# analog_part.net
KiCad netlist of a schematic drawn in Altium Designer
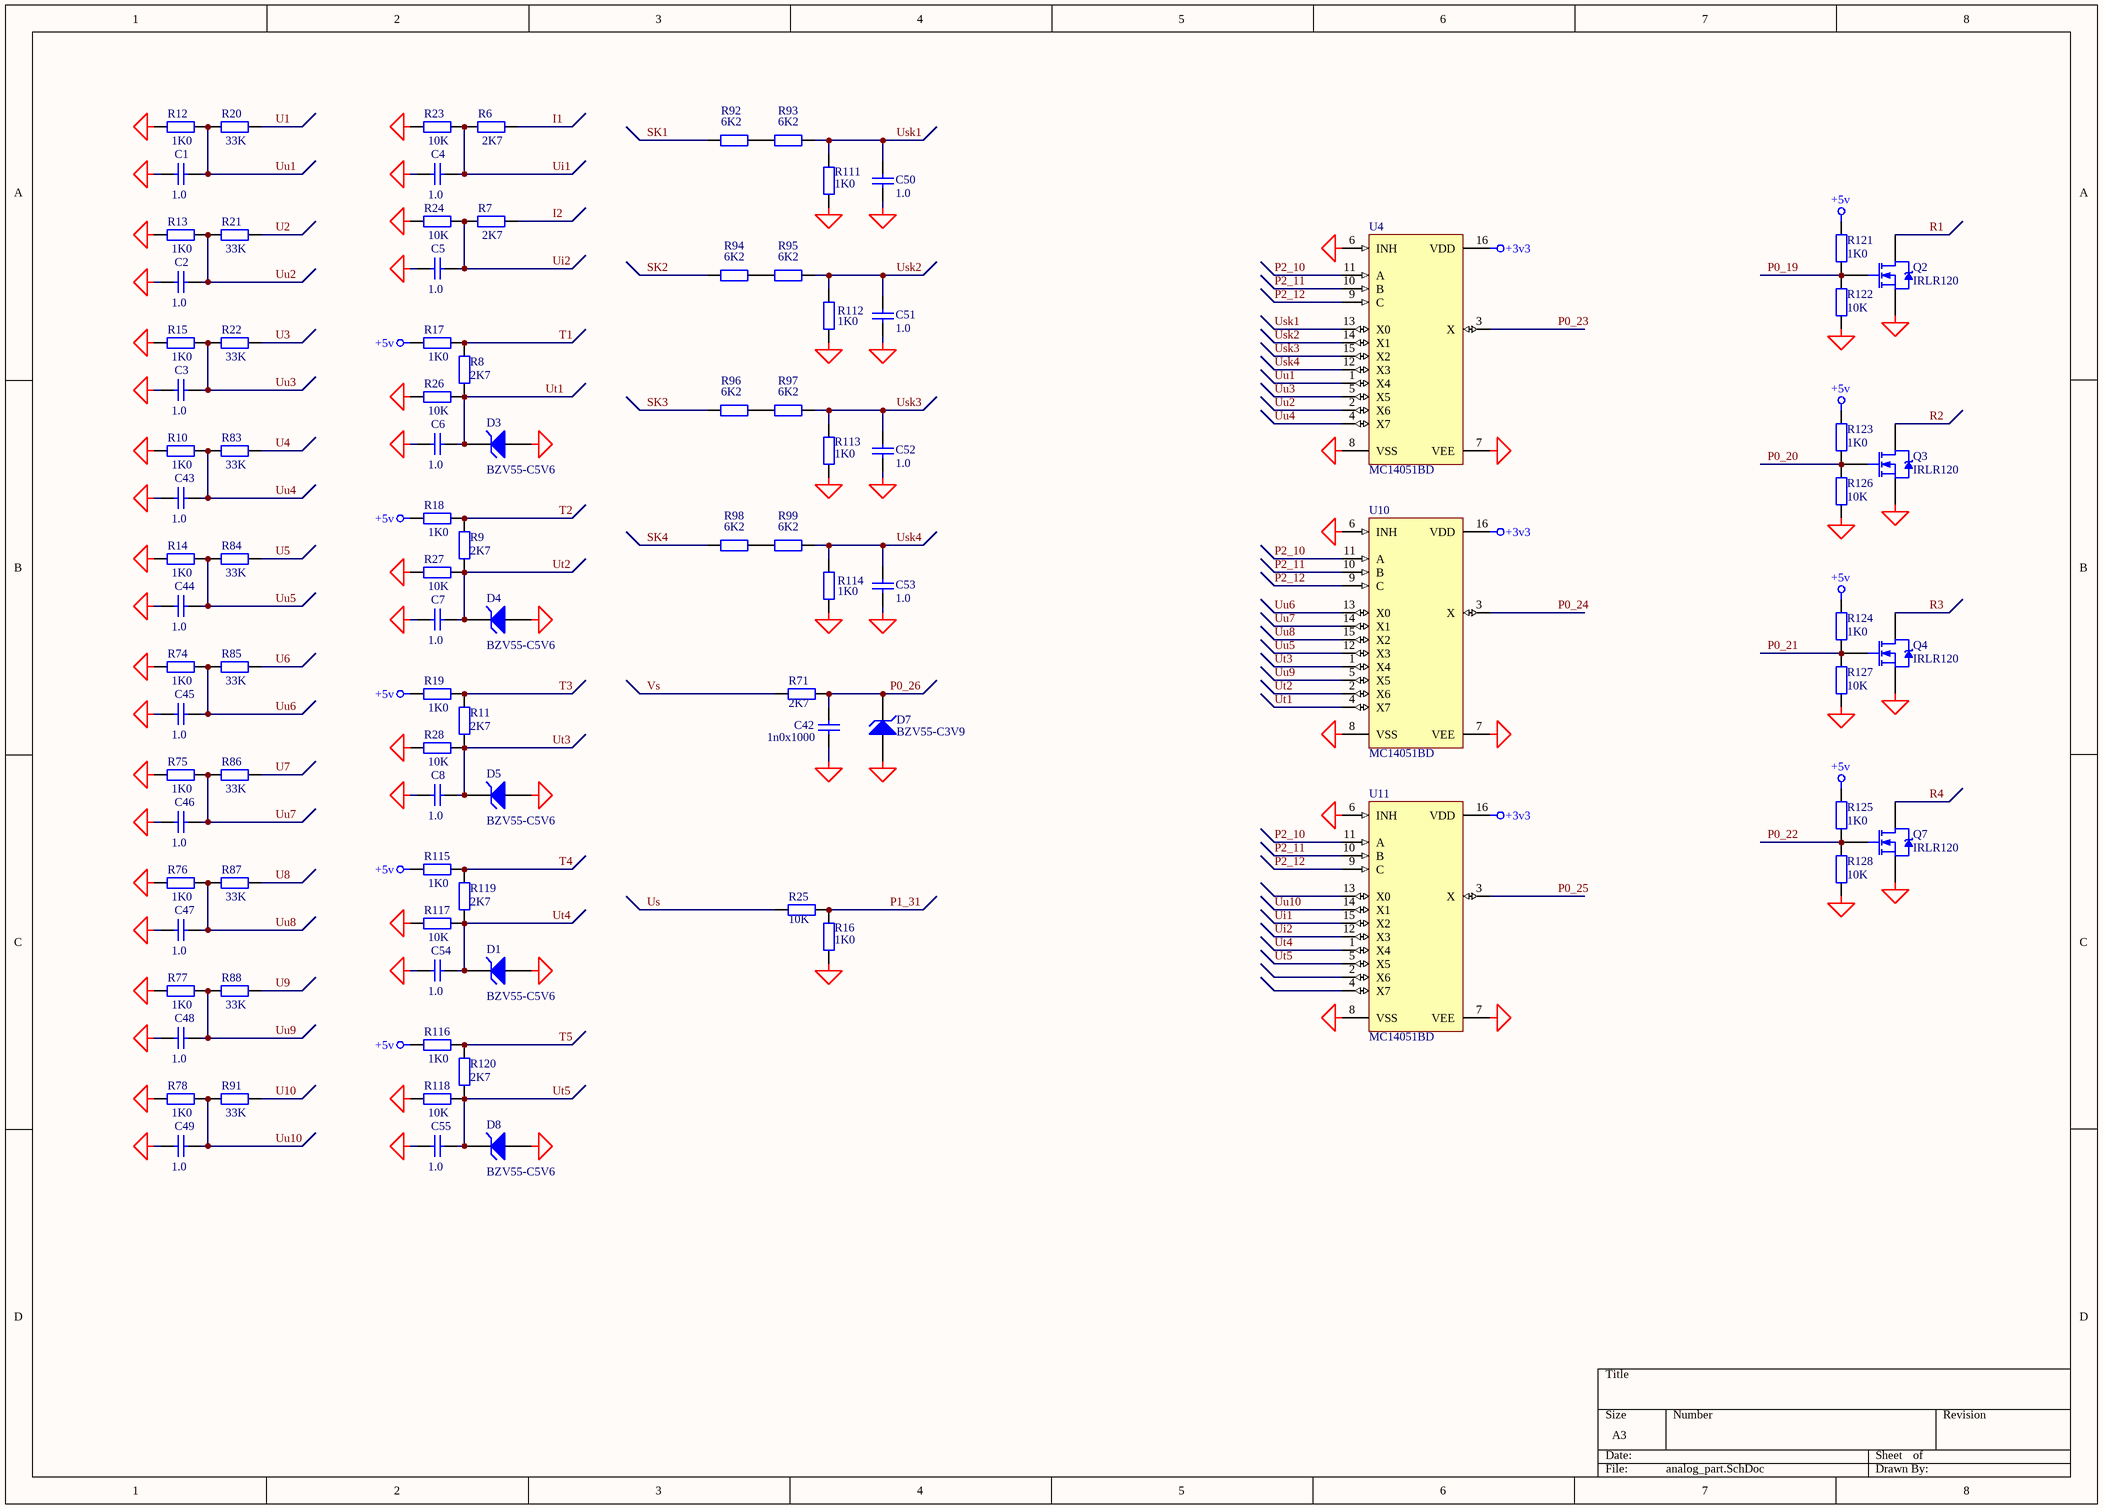
[diagram p0: analog_part.SchDoc]

(export (version "E")
  (design (tool "Eeschema 10.0.6"))
  (components
    (comp (ref "C1")
      (value "1.0")
      (footprint "_1206")
      (description "Capacitor (Semiconductor SIM Model)")
      (fields (field (name "MANUFACTURER") "Generic Components") (field (name "PUBLISHER") "Altium Limited"))
      (libsource (lib "Miscellaneous Devices") (part "Cap Semi"))
    )
    (comp (ref "C2")
      (value "1.0")
      (footprint "_1206")
      (description "Capacitor (Semiconductor SIM Model)")
      (fields (field (name "MANUFACTURER") "Generic Components") (field (name "PUBLISHER") "Altium Limited"))
      (libsource (lib "Miscellaneous Devices") (part "Cap Semi"))
    )
    (comp (ref "C3")
      (value "1.0")
      (footprint "_1206")
      (description "Capacitor (Semiconductor SIM Model)")
      (fields (field (name "MANUFACTURER") "Generic Components") (field (name "PUBLISHER") "Altium Limited"))
      (libsource (lib "Miscellaneous Devices") (part "Cap Semi"))
    )
    (comp (ref "C4")
      (value "1.0")
      (footprint "_1206")
      (description "Capacitor (Semiconductor SIM Model)")
      (fields (field (name "MANUFACTURER") "Generic Components") (field (name "PUBLISHER") "Altium Limited"))
      (libsource (lib "Miscellaneous Devices") (part "Cap Semi"))
    )
    (comp (ref "C5")
      (value "1.0")
      (footprint "_1206")
      (description "Capacitor (Semiconductor SIM Model)")
      (fields (field (name "MANUFACTURER") "Generic Components") (field (name "PUBLISHER") "Altium Limited"))
      (libsource (lib "Miscellaneous Devices") (part "Cap Semi"))
    )
    (comp (ref "C6")
      (value "1.0")
      (footprint "_1206")
      (description "Capacitor (Semiconductor SIM Model)")
      (fields (field (name "MANUFACTURER") "Generic Components") (field (name "PUBLISHER") "Altium Limited"))
      (libsource (lib "Miscellaneous Devices") (part "Cap Semi"))
    )
    (comp (ref "C7")
      (value "1.0")
      (footprint "_1206")
      (description "Capacitor (Semiconductor SIM Model)")
      (fields (field (name "MANUFACTURER") "Generic Components") (field (name "PUBLISHER") "Altium Limited"))
      (libsource (lib "Miscellaneous Devices") (part "Cap Semi"))
    )
    (comp (ref "C8")
      (value "1.0")
      (footprint "_1206")
      (description "Capacitor (Semiconductor SIM Model)")
      (fields (field (name "MANUFACTURER") "Generic Components") (field (name "PUBLISHER") "Altium Limited"))
      (libsource (lib "Miscellaneous Devices") (part "Cap Semi"))
    )
    (comp (ref "C42")
      (value "1n0x1000")
      (footprint "_1206")
      (description "Capacitor (Semiconductor SIM Model)")
      (fields (field (name "MANUFACTURER") "Generic Components") (field (name "PUBLISHER") "Altium Limited"))
      (libsource (lib "") (part "Cap Semi_1"))
    )
    (comp (ref "C43")
      (value "1.0")
      (footprint "_1206")
      (description "Capacitor (Semiconductor SIM Model)")
      (fields (field (name "MANUFACTURER") "Generic Components") (field (name "PUBLISHER") "Altium Limited"))
      (libsource (lib "Miscellaneous Devices") (part "Cap Semi"))
    )
    (comp (ref "C44")
      (value "1.0")
      (footprint "_1206")
      (description "Capacitor (Semiconductor SIM Model)")
      (fields (field (name "MANUFACTURER") "Generic Components") (field (name "PUBLISHER") "Altium Limited"))
      (libsource (lib "Miscellaneous Devices") (part "Cap Semi"))
    )
    (comp (ref "C45")
      (value "1.0")
      (footprint "_1206")
      (description "Capacitor (Semiconductor SIM Model)")
      (fields (field (name "MANUFACTURER") "Generic Components") (field (name "PUBLISHER") "Altium Limited"))
      (libsource (lib "Miscellaneous Devices") (part "Cap Semi"))
    )
    (comp (ref "C46")
      (value "1.0")
      (footprint "_1206")
      (description "Capacitor (Semiconductor SIM Model)")
      (fields (field (name "MANUFACTURER") "Generic Components") (field (name "PUBLISHER") "Altium Limited"))
      (libsource (lib "Miscellaneous Devices") (part "Cap Semi"))
    )
    (comp (ref "C47")
      (value "1.0")
      (footprint "_1206")
      (description "Capacitor (Semiconductor SIM Model)")
      (fields (field (name "MANUFACTURER") "Generic Components") (field (name "PUBLISHER") "Altium Limited"))
      (libsource (lib "Miscellaneous Devices") (part "Cap Semi"))
    )
    (comp (ref "C48")
      (value "1.0")
      (footprint "_1206")
      (description "Capacitor (Semiconductor SIM Model)")
      (fields (field (name "MANUFACTURER") "Generic Components") (field (name "PUBLISHER") "Altium Limited"))
      (libsource (lib "Miscellaneous Devices") (part "Cap Semi"))
    )
    (comp (ref "C49")
      (value "1.0")
      (footprint "_1206")
      (description "Capacitor (Semiconductor SIM Model)")
      (fields (field (name "MANUFACTURER") "Generic Components") (field (name "PUBLISHER") "Altium Limited"))
      (libsource (lib "Miscellaneous Devices") (part "Cap Semi"))
    )
    (comp (ref "C50")
      (value "1.0")
      (footprint "_1206")
      (description "Capacitor (Semiconductor SIM Model)")
      (fields (field (name "MANUFACTURER") "Generic Components") (field (name "PUBLISHER") "Altium Limited"))
      (libsource (lib "Miscellaneous Devices") (part "Cap Semi"))
    )
    (comp (ref "C51")
      (value "1.0")
      (footprint "_1206")
      (description "Capacitor (Semiconductor SIM Model)")
      (fields (field (name "MANUFACTURER") "Generic Components") (field (name "PUBLISHER") "Altium Limited"))
      (libsource (lib "Miscellaneous Devices") (part "Cap Semi"))
    )
    (comp (ref "C52")
      (value "1.0")
      (footprint "_1206")
      (description "Capacitor (Semiconductor SIM Model)")
      (fields (field (name "MANUFACTURER") "Generic Components") (field (name "PUBLISHER") "Altium Limited"))
      (libsource (lib "Miscellaneous Devices") (part "Cap Semi"))
    )
    (comp (ref "C53")
      (value "1.0")
      (footprint "_1206")
      (description "Capacitor (Semiconductor SIM Model)")
      (fields (field (name "MANUFACTURER") "Generic Components") (field (name "PUBLISHER") "Altium Limited"))
      (libsource (lib "Miscellaneous Devices") (part "Cap Semi"))
    )
    (comp (ref "C54")
      (value "1.0")
      (footprint "_1206")
      (description "Capacitor (Semiconductor SIM Model)")
      (fields (field (name "MANUFACTURER") "Generic Components") (field (name "PUBLISHER") "Altium Limited"))
      (libsource (lib "Miscellaneous Devices") (part "Cap Semi"))
    )
    (comp (ref "C55")
      (value "1.0")
      (footprint "_1206")
      (description "Capacitor (Semiconductor SIM Model)")
      (fields (field (name "MANUFACTURER") "Generic Components") (field (name "PUBLISHER") "Altium Limited"))
      (libsource (lib "Miscellaneous Devices") (part "Cap Semi"))
    )
    (comp (ref "D1")
      (value "BZV55-C5V6")
      (footprint "_1206d")
      (description "Zener Diode")
      (fields (field (name "MANUFACTURER") "Generic Components") (field (name "PUBLISHER") "Altium Limited"))
      (libsource (lib "Miscellaneous Devices") (part "D Zener"))
    )
    (comp (ref "D3")
      (value "BZV55-C5V6")
      (footprint "_1206d")
      (description "Zener Diode")
      (fields (field (name "MANUFACTURER") "Generic Components") (field (name "PUBLISHER") "Altium Limited"))
      (libsource (lib "Miscellaneous Devices") (part "D Zener"))
    )
    (comp (ref "D4")
      (value "BZV55-C5V6")
      (footprint "_1206d")
      (description "Zener Diode")
      (fields (field (name "MANUFACTURER") "Generic Components") (field (name "PUBLISHER") "Altium Limited"))
      (libsource (lib "Miscellaneous Devices") (part "D Zener"))
    )
    (comp (ref "D5")
      (value "BZV55-C5V6")
      (footprint "_1206d")
      (description "Zener Diode")
      (fields (field (name "MANUFACTURER") "Generic Components") (field (name "PUBLISHER") "Altium Limited"))
      (libsource (lib "Miscellaneous Devices") (part "D Zener"))
    )
    (comp (ref "D7")
      (value "BZV55-C3V9")
      (footprint "_1206d")
      (description "Zener Diode")
      (fields (field (name "MANUFACTURER") "Generic Components") (field (name "PUBLISHER") "Altium Limited"))
      (libsource (lib "") (part "D Zener_1"))
    )
    (comp (ref "D8")
      (value "BZV55-C5V6")
      (footprint "_1206d")
      (description "Zener Diode")
      (fields (field (name "MANUFACTURER") "Generic Components") (field (name "PUBLISHER") "Altium Limited"))
      (libsource (lib "Miscellaneous Devices") (part "D Zener"))
    )
    (comp (ref "Q2")
      (value "IRLR120")
      (footprint "SIP-G3/E8")
      (description "HEXFET N-Channel Power MOSFET")
      (fields
        (field (name "MANUFACTURER") "International Rectifier")
        (field (name "PUBLISHER") "Altium Limited")
      )
      (libsource (lib "IR Discrete MOSFET") (part "IRFR120"))
    )
    (comp (ref "Q3")
      (value "IRLR120")
      (footprint "SIP-G3/E8")
      (description "HEXFET N-Channel Power MOSFET")
      (fields
        (field (name "MANUFACTURER") "International Rectifier")
        (field (name "PUBLISHER") "Altium Limited")
      )
      (libsource (lib "IR Discrete MOSFET") (part "IRFR120"))
    )
    (comp (ref "Q4")
      (value "IRLR120")
      (footprint "SIP-G3/E8")
      (description "HEXFET N-Channel Power MOSFET")
      (fields
        (field (name "MANUFACTURER") "International Rectifier")
        (field (name "PUBLISHER") "Altium Limited")
      )
      (libsource (lib "IR Discrete MOSFET") (part "IRFR120"))
    )
    (comp (ref "Q7")
      (value "IRLR120")
      (footprint "SIP-G3/E8")
      (description "HEXFET N-Channel Power MOSFET")
      (fields
        (field (name "MANUFACTURER") "International Rectifier")
        (field (name "PUBLISHER") "Altium Limited")
      )
      (libsource (lib "IR Discrete MOSFET") (part "IRFR120"))
    )
    (comp (ref "R6")
      (value "2K7")
      (footprint "_1206")
      (description "Resistor")
      (fields (field (name "MANUFACTURER") "Generic Components") (field (name "PUBLISHER") "Altium Limited"))
      (libsource (lib "") (part "Res2_2"))
    )
    (comp (ref "R7")
      (value "2K7")
      (footprint "_1206")
      (description "Resistor")
      (fields (field (name "MANUFACTURER") "Generic Components") (field (name "PUBLISHER") "Altium Limited"))
      (libsource (lib "") (part "Res2_2"))
    )
    (comp (ref "R8")
      (value "2K7")
      (footprint "_1206")
      (description "Resistor")
      (fields (field (name "MANUFACTURER") "Generic Components") (field (name "PUBLISHER") "Altium Limited"))
      (libsource (lib "Miscellaneous Devices") (part "Res2"))
    )
    (comp (ref "R9")
      (value "2K7")
      (footprint "_1206")
      (description "Resistor")
      (fields (field (name "MANUFACTURER") "Generic Components") (field (name "PUBLISHER") "Altium Limited"))
      (libsource (lib "Miscellaneous Devices") (part "Res2"))
    )
    (comp (ref "R10")
      (value "1K0")
      (footprint "_1206")
      (description "Resistor")
      (fields (field (name "MANUFACTURER") "Generic Components") (field (name "PUBLISHER") "Altium Limited"))
      (libsource (lib "") (part "Res2_1"))
    )
    (comp (ref "R11")
      (value "2K7")
      (footprint "_1206")
      (description "Resistor")
      (fields (field (name "MANUFACTURER") "Generic Components") (field (name "PUBLISHER") "Altium Limited"))
      (libsource (lib "Miscellaneous Devices") (part "Res2"))
    )
    (comp (ref "R12")
      (value "1K0")
      (footprint "_1206")
      (description "Resistor")
      (fields (field (name "MANUFACTURER") "Generic Components") (field (name "PUBLISHER") "Altium Limited"))
      (libsource (lib "") (part "Res2_1"))
    )
    (comp (ref "R13")
      (value "1K0")
      (footprint "_1206")
      (description "Resistor")
      (fields (field (name "MANUFACTURER") "Generic Components") (field (name "PUBLISHER") "Altium Limited"))
      (libsource (lib "") (part "Res2_1"))
    )
    (comp (ref "R14")
      (value "1K0")
      (footprint "_1206")
      (description "Resistor")
      (fields (field (name "MANUFACTURER") "Generic Components") (field (name "PUBLISHER") "Altium Limited"))
      (libsource (lib "") (part "Res2_1"))
    )
    (comp (ref "R15")
      (value "1K0")
      (footprint "_1206")
      (description "Resistor")
      (fields (field (name "MANUFACTURER") "Generic Components") (field (name "PUBLISHER") "Altium Limited"))
      (libsource (lib "") (part "Res2_1"))
    )
    (comp (ref "R16")
      (value "1K0")
      (footprint "_1206")
      (description "Resistor")
      (fields (field (name "MANUFACTURER") "Generic Components") (field (name "PUBLISHER") "Altium Limited"))
      (libsource (lib "") (part "Res2_3"))
    )
    (comp (ref "R17")
      (value "1K0")
      (footprint "_1206")
      (description "Resistor")
      (fields (field (name "MANUFACTURER") "Generic Components") (field (name "PUBLISHER") "Altium Limited"))
      (libsource (lib "") (part "Res2_1"))
    )
    (comp (ref "R18")
      (value "1K0")
      (footprint "_1206")
      (description "Resistor")
      (fields (field (name "MANUFACTURER") "Generic Components") (field (name "PUBLISHER") "Altium Limited"))
      (libsource (lib "") (part "Res2_1"))
    )
    (comp (ref "R19")
      (value "1K0")
      (footprint "_1206")
      (description "Resistor")
      (fields (field (name "MANUFACTURER") "Generic Components") (field (name "PUBLISHER") "Altium Limited"))
      (libsource (lib "") (part "Res2_1"))
    )
    (comp (ref "R20")
      (value "33K")
      (footprint "_1206")
      (description "Resistor")
      (fields (field (name "MANUFACTURER") "Generic Components") (field (name "PUBLISHER") "Altium Limited"))
      (libsource (lib "") (part "Res2_2"))
    )
    (comp (ref "R21")
      (value "33K")
      (footprint "_1206")
      (description "Resistor")
      (fields (field (name "MANUFACTURER") "Generic Components") (field (name "PUBLISHER") "Altium Limited"))
      (libsource (lib "") (part "Res2_2"))
    )
    (comp (ref "R22")
      (value "33K")
      (footprint "_1206")
      (description "Resistor")
      (fields (field (name "MANUFACTURER") "Generic Components") (field (name "PUBLISHER") "Altium Limited"))
      (libsource (lib "") (part "Res2_2"))
    )
    (comp (ref "R23")
      (value "10K")
      (footprint "_1206")
      (description "Resistor")
      (fields (field (name "MANUFACTURER") "Generic Components") (field (name "PUBLISHER") "Altium Limited"))
      (libsource (lib "") (part "Res2_2"))
    )
    (comp (ref "R24")
      (value "10K")
      (footprint "_1206")
      (description "Resistor")
      (fields (field (name "MANUFACTURER") "Generic Components") (field (name "PUBLISHER") "Altium Limited"))
      (libsource (lib "") (part "Res2_2"))
    )
    (comp (ref "R25")
      (value "10K")
      (footprint "_1206")
      (description "Resistor")
      (fields (field (name "MANUFACTURER") "Generic Components") (field (name "PUBLISHER") "Altium Limited"))
      (libsource (lib "") (part "Res2_1"))
    )
    (comp (ref "R26")
      (value "10K")
      (footprint "_1206")
      (description "Resistor")
      (fields (field (name "MANUFACTURER") "Generic Components") (field (name "PUBLISHER") "Altium Limited"))
      (libsource (lib "") (part "Res2_2"))
    )
    (comp (ref "R27")
      (value "10K")
      (footprint "_1206")
      (description "Resistor")
      (fields (field (name "MANUFACTURER") "Generic Components") (field (name "PUBLISHER") "Altium Limited"))
      (libsource (lib "") (part "Res2_2"))
    )
    (comp (ref "R28")
      (value "10K")
      (footprint "_1206")
      (description "Resistor")
      (fields (field (name "MANUFACTURER") "Generic Components") (field (name "PUBLISHER") "Altium Limited"))
      (libsource (lib "") (part "Res2_2"))
    )
    (comp (ref "R71")
      (value "2K7")
      (footprint "_1206")
      (description "Resistor")
      (fields (field (name "MANUFACTURER") "Generic Components") (field (name "PUBLISHER") "Altium Limited"))
      (libsource (lib "") (part "Res2_4"))
    )
    (comp (ref "R74")
      (value "1K0")
      (footprint "_1206")
      (description "Resistor")
      (fields (field (name "MANUFACTURER") "Generic Components") (field (name "PUBLISHER") "Altium Limited"))
      (libsource (lib "") (part "Res2_1"))
    )
    (comp (ref "R75")
      (value "1K0")
      (footprint "_1206")
      (description "Resistor")
      (fields (field (name "MANUFACTURER") "Generic Components") (field (name "PUBLISHER") "Altium Limited"))
      (libsource (lib "") (part "Res2_1"))
    )
    (comp (ref "R76")
      (value "1K0")
      (footprint "_1206")
      (description "Resistor")
      (fields (field (name "MANUFACTURER") "Generic Components") (field (name "PUBLISHER") "Altium Limited"))
      (libsource (lib "") (part "Res2_1"))
    )
    (comp (ref "R77")
      (value "1K0")
      (footprint "_1206")
      (description "Resistor")
      (fields (field (name "MANUFACTURER") "Generic Components") (field (name "PUBLISHER") "Altium Limited"))
      (libsource (lib "") (part "Res2_1"))
    )
    (comp (ref "R78")
      (value "1K0")
      (footprint "_1206")
      (description "Resistor")
      (fields (field (name "MANUFACTURER") "Generic Components") (field (name "PUBLISHER") "Altium Limited"))
      (libsource (lib "") (part "Res2_1"))
    )
    (comp (ref "R83")
      (value "33K")
      (footprint "_1206")
      (description "Resistor")
      (fields (field (name "MANUFACTURER") "Generic Components") (field (name "PUBLISHER") "Altium Limited"))
      (libsource (lib "") (part "Res2_2"))
    )
    (comp (ref "R84")
      (value "33K")
      (footprint "_1206")
      (description "Resistor")
      (fields (field (name "MANUFACTURER") "Generic Components") (field (name "PUBLISHER") "Altium Limited"))
      (libsource (lib "") (part "Res2_2"))
    )
    (comp (ref "R85")
      (value "33K")
      (footprint "_1206")
      (description "Resistor")
      (fields (field (name "MANUFACTURER") "Generic Components") (field (name "PUBLISHER") "Altium Limited"))
      (libsource (lib "") (part "Res2_2"))
    )
    (comp (ref "R86")
      (value "33K")
      (footprint "_1206")
      (description "Resistor")
      (fields (field (name "MANUFACTURER") "Generic Components") (field (name "PUBLISHER") "Altium Limited"))
      (libsource (lib "") (part "Res2_2"))
    )
    (comp (ref "R87")
      (value "33K")
      (footprint "_1206")
      (description "Resistor")
      (fields (field (name "MANUFACTURER") "Generic Components") (field (name "PUBLISHER") "Altium Limited"))
      (libsource (lib "") (part "Res2_2"))
    )
    (comp (ref "R88")
      (value "33K")
      (footprint "_1206")
      (description "Resistor")
      (fields (field (name "MANUFACTURER") "Generic Components") (field (name "PUBLISHER") "Altium Limited"))
      (libsource (lib "") (part "Res2_2"))
    )
    (comp (ref "R91")
      (value "33K")
      (footprint "_1206")
      (description "Resistor")
      (fields (field (name "MANUFACTURER") "Generic Components") (field (name "PUBLISHER") "Altium Limited"))
      (libsource (lib "") (part "Res2_2"))
    )
    (comp (ref "R92")
      (value "6K2")
      (footprint "_1206")
      (description "Resistor")
      (fields (field (name "MANUFACTURER") "Generic Components") (field (name "PUBLISHER") "Altium Limited"))
      (libsource (lib "") (part "Res2_2"))
    )
    (comp (ref "R93")
      (value "6K2")
      (footprint "_1206")
      (description "Resistor")
      (fields (field (name "MANUFACTURER") "Generic Components") (field (name "PUBLISHER") "Altium Limited"))
      (libsource (lib "") (part "Res2_2"))
    )
    (comp (ref "R94")
      (value "6K2")
      (footprint "_1206")
      (description "Resistor")
      (fields (field (name "MANUFACTURER") "Generic Components") (field (name "PUBLISHER") "Altium Limited"))
      (libsource (lib "") (part "Res2_2"))
    )
    (comp (ref "R95")
      (value "6K2")
      (footprint "_1206")
      (description "Resistor")
      (fields (field (name "MANUFACTURER") "Generic Components") (field (name "PUBLISHER") "Altium Limited"))
      (libsource (lib "") (part "Res2_2"))
    )
    (comp (ref "R96")
      (value "6K2")
      (footprint "_1206")
      (description "Resistor")
      (fields (field (name "MANUFACTURER") "Generic Components") (field (name "PUBLISHER") "Altium Limited"))
      (libsource (lib "") (part "Res2_2"))
    )
    (comp (ref "R97")
      (value "6K2")
      (footprint "_1206")
      (description "Resistor")
      (fields (field (name "MANUFACTURER") "Generic Components") (field (name "PUBLISHER") "Altium Limited"))
      (libsource (lib "") (part "Res2_2"))
    )
    (comp (ref "R98")
      (value "6K2")
      (footprint "_1206")
      (description "Resistor")
      (fields (field (name "MANUFACTURER") "Generic Components") (field (name "PUBLISHER") "Altium Limited"))
      (libsource (lib "") (part "Res2_2"))
    )
    (comp (ref "R99")
      (value "6K2")
      (footprint "_1206")
      (description "Resistor")
      (fields (field (name "MANUFACTURER") "Generic Components") (field (name "PUBLISHER") "Altium Limited"))
      (libsource (lib "") (part "Res2_2"))
    )
    (comp (ref "R111")
      (value "1K0")
      (footprint "_1206")
      (description "Resistor")
      (fields (field (name "MANUFACTURER") "Generic Components") (field (name "PUBLISHER") "Altium Limited"))
      (libsource (lib "Miscellaneous Devices") (part "Res2"))
    )
    (comp (ref "R112")
      (value "1K0")
      (footprint "_1206")
      (description "Resistor")
      (fields (field (name "MANUFACTURER") "Generic Components") (field (name "PUBLISHER") "Altium Limited"))
      (libsource (lib "Miscellaneous Devices") (part "Res2"))
    )
    (comp (ref "R113")
      (value "1K0")
      (footprint "_1206")
      (description "Resistor")
      (fields (field (name "MANUFACTURER") "Generic Components") (field (name "PUBLISHER") "Altium Limited"))
      (libsource (lib "Miscellaneous Devices") (part "Res2"))
    )
    (comp (ref "R114")
      (value "1K0")
      (footprint "_1206")
      (description "Resistor")
      (fields (field (name "MANUFACTURER") "Generic Components") (field (name "PUBLISHER") "Altium Limited"))
      (libsource (lib "Miscellaneous Devices") (part "Res2"))
    )
    (comp (ref "R115")
      (value "1K0")
      (footprint "_1206")
      (description "Resistor")
      (fields (field (name "MANUFACTURER") "Generic Components") (field (name "PUBLISHER") "Altium Limited"))
      (libsource (lib "") (part "Res2_1"))
    )
    (comp (ref "R116")
      (value "1K0")
      (footprint "_1206")
      (description "Resistor")
      (fields (field (name "MANUFACTURER") "Generic Components") (field (name "PUBLISHER") "Altium Limited"))
      (libsource (lib "") (part "Res2_1"))
    )
    (comp (ref "R117")
      (value "10K")
      (footprint "_1206")
      (description "Resistor")
      (fields (field (name "MANUFACTURER") "Generic Components") (field (name "PUBLISHER") "Altium Limited"))
      (libsource (lib "") (part "Res2_2"))
    )
    (comp (ref "R118")
      (value "10K")
      (footprint "_1206")
      (description "Resistor")
      (fields (field (name "MANUFACTURER") "Generic Components") (field (name "PUBLISHER") "Altium Limited"))
      (libsource (lib "") (part "Res2_2"))
    )
    (comp (ref "R119")
      (value "2K7")
      (footprint "_1206")
      (description "Resistor")
      (fields (field (name "MANUFACTURER") "Generic Components") (field (name "PUBLISHER") "Altium Limited"))
      (libsource (lib "Miscellaneous Devices") (part "Res2"))
    )
    (comp (ref "R120")
      (value "2K7")
      (footprint "_1206")
      (description "Resistor")
      (fields (field (name "MANUFACTURER") "Generic Components") (field (name "PUBLISHER") "Altium Limited"))
      (libsource (lib "Miscellaneous Devices") (part "Res2"))
    )
    (comp (ref "R121")
      (value "1K0")
      (footprint "_1206")
      (description "Resistor")
      (fields (field (name "MANUFACTURER") "Generic Components") (field (name "PUBLISHER") "Altium Limited"))
      (libsource (lib "Miscellaneous Devices") (part "Res2"))
    )
    (comp (ref "R122")
      (value "10K")
      (footprint "_1206")
      (description "Resistor")
      (fields (field (name "MANUFACTURER") "Generic Components") (field (name "PUBLISHER") "Altium Limited"))
      (libsource (lib "") (part "Res2_3"))
    )
    (comp (ref "R123")
      (value "1K0")
      (footprint "_1206")
      (description "Resistor")
      (fields (field (name "MANUFACTURER") "Generic Components") (field (name "PUBLISHER") "Altium Limited"))
      (libsource (lib "Miscellaneous Devices") (part "Res2"))
    )
    (comp (ref "R124")
      (value "1K0")
      (footprint "_1206")
      (description "Resistor")
      (fields (field (name "MANUFACTURER") "Generic Components") (field (name "PUBLISHER") "Altium Limited"))
      (libsource (lib "Miscellaneous Devices") (part "Res2"))
    )
    (comp (ref "R125")
      (value "1K0")
      (footprint "_1206")
      (description "Resistor")
      (fields (field (name "MANUFACTURER") "Generic Components") (field (name "PUBLISHER") "Altium Limited"))
      (libsource (lib "Miscellaneous Devices") (part "Res2"))
    )
    (comp (ref "R126")
      (value "10K")
      (footprint "_1206")
      (description "Resistor")
      (fields (field (name "MANUFACTURER") "Generic Components") (field (name "PUBLISHER") "Altium Limited"))
      (libsource (lib "") (part "Res2_3"))
    )
    (comp (ref "R127")
      (value "10K")
      (footprint "_1206")
      (description "Resistor")
      (fields (field (name "MANUFACTURER") "Generic Components") (field (name "PUBLISHER") "Altium Limited"))
      (libsource (lib "") (part "Res2_3"))
    )
    (comp (ref "R128")
      (value "10K")
      (footprint "_1206")
      (description "Resistor")
      (fields (field (name "MANUFACTURER") "Generic Components") (field (name "PUBLISHER") "Altium Limited"))
      (libsource (lib "") (part "Res2_3"))
    )
    (comp (ref "U4")
      (value "MC14051BD")
      (footprint "SO-G16/C5.85")
      (description "8-Channel Analog Multiplexer/Demultiplexer")
      (fields (field (name "MANUFACTURER") "ON Semiconductor") (field (name "PUBLISHER") "Altium Limited"))
      (libsource (lib "ON Semi Logic Multiplexer") (part "MC14051BD"))
    )
    (comp (ref "U10")
      (value "MC14051BD")
      (footprint "SO-G16/C5.85")
      (description "8-Channel Analog Multiplexer/Demultiplexer")
      (fields (field (name "MANUFACTURER") "ON Semiconductor") (field (name "PUBLISHER") "Altium Limited"))
      (libsource (lib "ON Semi Logic Multiplexer") (part "MC14051BD"))
    )
    (comp (ref "U11")
      (value "MC14051BD")
      (footprint "SO-G16/C5.85")
      (description "8-Channel Analog Multiplexer/Demultiplexer")
      (fields (field (name "MANUFACTURER") "ON Semiconductor") (field (name "PUBLISHER") "Altium Limited"))
      (libsource (lib "ON Semi Logic Multiplexer") (part "MC14051BD"))
    )
  )
  (nets
    (net (code "1") (name "+3v3") (class "Default")
      (node (ref "U10") (pin "16") (pinfunction "VDD_16") (pintype "power_in"))
      (node (ref "U11") (pin "16") (pinfunction "VDD_16") (pintype "power_in"))
      (node (ref "U4") (pin "16") (pinfunction "VDD_16") (pintype "power_in"))
    )
    (net (code "2") (name "+5v") (class "Default")
      (node (ref "R115") (pin "2") (pinfunction "2_2") (pintype "passive"))
      (node (ref "R116") (pin "2") (pinfunction "2_2") (pintype "passive"))
      (node (ref "R121") (pin "2") (pinfunction "2_2") (pintype "passive"))
      (node (ref "R123") (pin "2") (pinfunction "2_2") (pintype "passive"))
      (node (ref "R124") (pin "2") (pinfunction "2_2") (pintype "passive"))
      (node (ref "R125") (pin "2") (pinfunction "2_2") (pintype "passive"))
      (node (ref "R17") (pin "2") (pinfunction "2_2") (pintype "passive"))
      (node (ref "R18") (pin "2") (pinfunction "2_2") (pintype "passive"))
      (node (ref "R19") (pin "2") (pinfunction "2_2") (pintype "passive"))
    )
    (net (code "3") (name "/I1") (class "Default")
      (node (ref "R6") (pin "2") (pinfunction "2_2") (pintype "passive"))
    )
    (net (code "4") (name "/I2") (class "Default")
      (node (ref "R7") (pin "2") (pinfunction "2_2") (pintype "passive"))
    )
    (net (code "5") (name "/P0_19") (class "Default")
      (node (ref "Q2") (pin "1") (pinfunction "G_1") (pintype "passive"))
      (node (ref "R121") (pin "1") (pinfunction "1_1") (pintype "passive"))
      (node (ref "R122") (pin "1") (pinfunction "1_1") (pintype "passive"))
    )
    (net (code "6") (name "/P0_20") (class "Default")
      (node (ref "Q3") (pin "1") (pinfunction "G_1") (pintype "passive"))
      (node (ref "R123") (pin "1") (pinfunction "1_1") (pintype "passive"))
      (node (ref "R126") (pin "1") (pinfunction "1_1") (pintype "passive"))
    )
    (net (code "7") (name "/P0_21") (class "Default")
      (node (ref "Q4") (pin "1") (pinfunction "G_1") (pintype "passive"))
      (node (ref "R124") (pin "1") (pinfunction "1_1") (pintype "passive"))
      (node (ref "R127") (pin "1") (pinfunction "1_1") (pintype "passive"))
    )
    (net (code "8") (name "/P0_22") (class "Default")
      (node (ref "Q7") (pin "1") (pinfunction "G_1") (pintype "passive"))
      (node (ref "R125") (pin "1") (pinfunction "1_1") (pintype "passive"))
      (node (ref "R128") (pin "1") (pinfunction "1_1") (pintype "passive"))
    )
    (net (code "9") (name "/P0_23") (class "Default")
      (node (ref "U4") (pin "3") (pinfunction "X_3") (pintype "bidirectional"))
    )
    (net (code "10") (name "/P0_24") (class "Default")
      (node (ref "U10") (pin "3") (pinfunction "X_3") (pintype "bidirectional"))
    )
    (net (code "11") (name "/P0_25") (class "Default")
      (node (ref "U11") (pin "3") (pinfunction "X_3") (pintype "bidirectional"))
    )
    (net (code "12") (name "/P0_26") (class "Default")
      (node (ref "C42") (pin "1") (pinfunction "1_1") (pintype "passive"))
      (node (ref "D7") (pin "2") (pinfunction "K_2") (pintype "passive"))
      (node (ref "R71") (pin "1") (pinfunction "1_1") (pintype "passive"))
    )
    (net (code "13") (name "/P1_31") (class "Default")
      (node (ref "R16") (pin "1") (pinfunction "1_1") (pintype "passive"))
      (node (ref "R25") (pin "1") (pinfunction "1_1") (pintype "passive"))
    )
    (net (code "14") (name "/P2_10") (class "Default")
      (node (ref "U10") (pin "11") (pinfunction "A_11") (pintype "input"))
      (node (ref "U11") (pin "11") (pinfunction "A_11") (pintype "input"))
      (node (ref "U4") (pin "11") (pinfunction "A_11") (pintype "input"))
    )
    (net (code "15") (name "/P2_11") (class "Default")
      (node (ref "U10") (pin "10") (pinfunction "B_10") (pintype "input"))
      (node (ref "U11") (pin "10") (pinfunction "B_10") (pintype "input"))
      (node (ref "U4") (pin "10") (pinfunction "B_10") (pintype "input"))
    )
    (net (code "16") (name "/P2_12") (class "Default")
      (node (ref "U10") (pin "9") (pinfunction "C_9") (pintype "input"))
      (node (ref "U11") (pin "9") (pinfunction "C_9") (pintype "input"))
      (node (ref "U4") (pin "9") (pinfunction "C_9") (pintype "input"))
    )
    (net (code "17") (name "/R1") (class "Default")
      (node (ref "Q2") (pin "4") (pinfunction "D_4") (pintype "passive"))
    )
    (net (code "18") (name "/R2") (class "Default")
      (node (ref "Q3") (pin "4") (pinfunction "D_4") (pintype "passive"))
    )
    (net (code "19") (name "/R3") (class "Default")
      (node (ref "Q4") (pin "4") (pinfunction "D_4") (pintype "passive"))
    )
    (net (code "20") (name "/R4") (class "Default")
      (node (ref "Q7") (pin "4") (pinfunction "D_4") (pintype "passive"))
    )
    (net (code "21") (name "/SK1") (class "Default")
      (node (ref "R92") (pin "1") (pinfunction "1_1") (pintype "passive"))
    )
    (net (code "22") (name "/SK2") (class "Default")
      (node (ref "R94") (pin "1") (pinfunction "1_1") (pintype "passive"))
    )
    (net (code "23") (name "/SK3") (class "Default")
      (node (ref "R96") (pin "1") (pinfunction "1_1") (pintype "passive"))
    )
    (net (code "24") (name "/SK4") (class "Default")
      (node (ref "R98") (pin "1") (pinfunction "1_1") (pintype "passive"))
    )
    (net (code "25") (name "/T1") (class "Default")
      (node (ref "R17") (pin "1") (pinfunction "1_1") (pintype "passive"))
      (node (ref "R8") (pin "2") (pinfunction "2_2") (pintype "passive"))
    )
    (net (code "26") (name "/T2") (class "Default")
      (node (ref "R18") (pin "1") (pinfunction "1_1") (pintype "passive"))
      (node (ref "R9") (pin "2") (pinfunction "2_2") (pintype "passive"))
    )
    (net (code "27") (name "/T3") (class "Default")
      (node (ref "R11") (pin "2") (pinfunction "2_2") (pintype "passive"))
      (node (ref "R19") (pin "1") (pinfunction "1_1") (pintype "passive"))
    )
    (net (code "28") (name "/T4") (class "Default")
      (node (ref "R115") (pin "1") (pinfunction "1_1") (pintype "passive"))
      (node (ref "R119") (pin "2") (pinfunction "2_2") (pintype "passive"))
    )
    (net (code "29") (name "/T5") (class "Default")
      (node (ref "R116") (pin "1") (pinfunction "1_1") (pintype "passive"))
      (node (ref "R120") (pin "2") (pinfunction "2_2") (pintype "passive"))
    )
    (net (code "30") (name "/U1") (class "Default")
      (node (ref "R20") (pin "2") (pinfunction "2_2") (pintype "passive"))
    )
    (net (code "31") (name "/U2") (class "Default")
      (node (ref "R21") (pin "2") (pinfunction "2_2") (pintype "passive"))
    )
    (net (code "32") (name "/U3") (class "Default")
      (node (ref "R22") (pin "2") (pinfunction "2_2") (pintype "passive"))
    )
    (net (code "33") (name "/U4") (class "Default")
      (node (ref "R83") (pin "2") (pinfunction "2_2") (pintype "passive"))
    )
    (net (code "34") (name "/U5") (class "Default")
      (node (ref "R84") (pin "2") (pinfunction "2_2") (pintype "passive"))
    )
    (net (code "35") (name "/U6") (class "Default")
      (node (ref "R85") (pin "2") (pinfunction "2_2") (pintype "passive"))
    )
    (net (code "36") (name "/U7") (class "Default")
      (node (ref "R86") (pin "2") (pinfunction "2_2") (pintype "passive"))
    )
    (net (code "37") (name "/U8") (class "Default")
      (node (ref "R87") (pin "2") (pinfunction "2_2") (pintype "passive"))
    )
    (net (code "38") (name "/U9") (class "Default")
      (node (ref "R88") (pin "2") (pinfunction "2_2") (pintype "passive"))
    )
    (net (code "39") (name "/U10") (class "Default")
      (node (ref "R91") (pin "2") (pinfunction "2_2") (pintype "passive"))
    )
    (net (code "40") (name "/Ui1") (class "Default")
      (node (ref "C4") (pin "1") (pinfunction "1_1") (pintype "passive"))
      (node (ref "R23") (pin "2") (pinfunction "2_2") (pintype "passive"))
      (node (ref "R6") (pin "1") (pinfunction "1_1") (pintype "passive"))
      (node (ref "U11") (pin "15") (pinfunction "X2_15") (pintype "bidirectional"))
    )
    (net (code "41") (name "/Ui2") (class "Default")
      (node (ref "C5") (pin "1") (pinfunction "1_1") (pintype "passive"))
      (node (ref "R24") (pin "2") (pinfunction "2_2") (pintype "passive"))
      (node (ref "R7") (pin "1") (pinfunction "1_1") (pintype "passive"))
      (node (ref "U11") (pin "12") (pinfunction "X3_12") (pintype "bidirectional"))
    )
    (net (code "42") (name "/Us") (class "Default")
      (node (ref "R25") (pin "2") (pinfunction "2_2") (pintype "passive"))
    )
    (net (code "43") (name "/Usk1") (class "Default")
      (node (ref "C50") (pin "1") (pinfunction "1_1") (pintype "passive"))
      (node (ref "R111") (pin "2") (pinfunction "2_2") (pintype "passive"))
      (node (ref "R93") (pin "2") (pinfunction "2_2") (pintype "passive"))
      (node (ref "U4") (pin "13") (pinfunction "X0_13") (pintype "bidirectional"))
    )
    (net (code "44") (name "/Usk2") (class "Default")
      (node (ref "C51") (pin "1") (pinfunction "1_1") (pintype "passive"))
      (node (ref "R112") (pin "2") (pinfunction "2_2") (pintype "passive"))
      (node (ref "R95") (pin "2") (pinfunction "2_2") (pintype "passive"))
      (node (ref "U4") (pin "14") (pinfunction "X1_14") (pintype "bidirectional"))
    )
    (net (code "45") (name "/Usk3") (class "Default")
      (node (ref "C52") (pin "1") (pinfunction "1_1") (pintype "passive"))
      (node (ref "R113") (pin "2") (pinfunction "2_2") (pintype "passive"))
      (node (ref "R97") (pin "2") (pinfunction "2_2") (pintype "passive"))
      (node (ref "U4") (pin "15") (pinfunction "X2_15") (pintype "bidirectional"))
    )
    (net (code "46") (name "/Usk4") (class "Default")
      (node (ref "C53") (pin "1") (pinfunction "1_1") (pintype "passive"))
      (node (ref "R114") (pin "2") (pinfunction "2_2") (pintype "passive"))
      (node (ref "R99") (pin "2") (pinfunction "2_2") (pintype "passive"))
      (node (ref "U4") (pin "12") (pinfunction "X3_12") (pintype "bidirectional"))
    )
    (net (code "47") (name "/Ut1") (class "Default")
      (node (ref "C6") (pin "1") (pinfunction "1_1") (pintype "passive"))
      (node (ref "D3") (pin "2") (pinfunction "K_2") (pintype "passive"))
      (node (ref "R26") (pin "2") (pinfunction "2_2") (pintype "passive"))
      (node (ref "R8") (pin "1") (pinfunction "1_1") (pintype "passive"))
      (node (ref "U10") (pin "4") (pinfunction "X7_4") (pintype "bidirectional"))
    )
    (net (code "48") (name "/Ut2") (class "Default")
      (node (ref "C7") (pin "1") (pinfunction "1_1") (pintype "passive"))
      (node (ref "D4") (pin "2") (pinfunction "K_2") (pintype "passive"))
      (node (ref "R27") (pin "2") (pinfunction "2_2") (pintype "passive"))
      (node (ref "R9") (pin "1") (pinfunction "1_1") (pintype "passive"))
      (node (ref "U10") (pin "2") (pinfunction "X6_2") (pintype "bidirectional"))
    )
    (net (code "49") (name "/Ut3") (class "Default")
      (node (ref "C8") (pin "1") (pinfunction "1_1") (pintype "passive"))
      (node (ref "D5") (pin "2") (pinfunction "K_2") (pintype "passive"))
      (node (ref "R11") (pin "1") (pinfunction "1_1") (pintype "passive"))
      (node (ref "R28") (pin "2") (pinfunction "2_2") (pintype "passive"))
      (node (ref "U10") (pin "1") (pinfunction "X4_1") (pintype "bidirectional"))
    )
    (net (code "50") (name "/Ut4") (class "Default")
      (node (ref "C54") (pin "1") (pinfunction "1_1") (pintype "passive"))
      (node (ref "D1") (pin "2") (pinfunction "K_2") (pintype "passive"))
      (node (ref "R117") (pin "2") (pinfunction "2_2") (pintype "passive"))
      (node (ref "R119") (pin "1") (pinfunction "1_1") (pintype "passive"))
      (node (ref "U11") (pin "1") (pinfunction "X4_1") (pintype "bidirectional"))
    )
    (net (code "51") (name "/Ut5") (class "Default")
      (node (ref "C55") (pin "1") (pinfunction "1_1") (pintype "passive"))
      (node (ref "D8") (pin "2") (pinfunction "K_2") (pintype "passive"))
      (node (ref "R118") (pin "2") (pinfunction "2_2") (pintype "passive"))
      (node (ref "R120") (pin "1") (pinfunction "1_1") (pintype "passive"))
      (node (ref "U11") (pin "5") (pinfunction "X5_5") (pintype "bidirectional"))
    )
    (net (code "52") (name "/Uu1") (class "Default")
      (node (ref "C1") (pin "1") (pinfunction "1_1") (pintype "passive"))
      (node (ref "R12") (pin "1") (pinfunction "1_1") (pintype "passive"))
      (node (ref "R20") (pin "1") (pinfunction "1_1") (pintype "passive"))
      (node (ref "U4") (pin "1") (pinfunction "X4_1") (pintype "bidirectional"))
    )
    (net (code "53") (name "/Uu2") (class "Default")
      (node (ref "C2") (pin "1") (pinfunction "1_1") (pintype "passive"))
      (node (ref "R13") (pin "1") (pinfunction "1_1") (pintype "passive"))
      (node (ref "R21") (pin "1") (pinfunction "1_1") (pintype "passive"))
      (node (ref "U4") (pin "2") (pinfunction "X6_2") (pintype "bidirectional"))
    )
    (net (code "54") (name "/Uu3") (class "Default")
      (node (ref "C3") (pin "1") (pinfunction "1_1") (pintype "passive"))
      (node (ref "R15") (pin "1") (pinfunction "1_1") (pintype "passive"))
      (node (ref "R22") (pin "1") (pinfunction "1_1") (pintype "passive"))
      (node (ref "U4") (pin "5") (pinfunction "X5_5") (pintype "bidirectional"))
    )
    (net (code "55") (name "/Uu4") (class "Default")
      (node (ref "C43") (pin "1") (pinfunction "1_1") (pintype "passive"))
      (node (ref "R10") (pin "1") (pinfunction "1_1") (pintype "passive"))
      (node (ref "R83") (pin "1") (pinfunction "1_1") (pintype "passive"))
      (node (ref "U4") (pin "4") (pinfunction "X7_4") (pintype "bidirectional"))
    )
    (net (code "56") (name "/Uu5") (class "Default")
      (node (ref "C44") (pin "1") (pinfunction "1_1") (pintype "passive"))
      (node (ref "R14") (pin "1") (pinfunction "1_1") (pintype "passive"))
      (node (ref "R84") (pin "1") (pinfunction "1_1") (pintype "passive"))
      (node (ref "U10") (pin "12") (pinfunction "X3_12") (pintype "bidirectional"))
    )
    (net (code "57") (name "/Uu6") (class "Default")
      (node (ref "C45") (pin "1") (pinfunction "1_1") (pintype "passive"))
      (node (ref "R74") (pin "1") (pinfunction "1_1") (pintype "passive"))
      (node (ref "R85") (pin "1") (pinfunction "1_1") (pintype "passive"))
      (node (ref "U10") (pin "13") (pinfunction "X0_13") (pintype "bidirectional"))
    )
    (net (code "58") (name "/Uu7") (class "Default")
      (node (ref "C46") (pin "1") (pinfunction "1_1") (pintype "passive"))
      (node (ref "R75") (pin "1") (pinfunction "1_1") (pintype "passive"))
      (node (ref "R86") (pin "1") (pinfunction "1_1") (pintype "passive"))
      (node (ref "U10") (pin "14") (pinfunction "X1_14") (pintype "bidirectional"))
    )
    (net (code "59") (name "/Uu8") (class "Default")
      (node (ref "C47") (pin "1") (pinfunction "1_1") (pintype "passive"))
      (node (ref "R76") (pin "1") (pinfunction "1_1") (pintype "passive"))
      (node (ref "R87") (pin "1") (pinfunction "1_1") (pintype "passive"))
      (node (ref "U10") (pin "15") (pinfunction "X2_15") (pintype "bidirectional"))
    )
    (net (code "60") (name "/Uu9") (class "Default")
      (node (ref "C48") (pin "1") (pinfunction "1_1") (pintype "passive"))
      (node (ref "R77") (pin "1") (pinfunction "1_1") (pintype "passive"))
      (node (ref "R88") (pin "1") (pinfunction "1_1") (pintype "passive"))
      (node (ref "U10") (pin "5") (pinfunction "X5_5") (pintype "bidirectional"))
    )
    (net (code "61") (name "/Uu10") (class "Default")
      (node (ref "C49") (pin "1") (pinfunction "1_1") (pintype "passive"))
      (node (ref "R78") (pin "1") (pinfunction "1_1") (pintype "passive"))
      (node (ref "R91") (pin "1") (pinfunction "1_1") (pintype "passive"))
      (node (ref "U11") (pin "14") (pinfunction "X1_14") (pintype "bidirectional"))
    )
    (net (code "62") (name "/Vs") (class "Default")
      (node (ref "R71") (pin "2") (pinfunction "2_2") (pintype "passive"))
    )
    (net (code "63") (name "GND") (class "Default")
      (node (ref "C1") (pin "2") (pinfunction "2_2") (pintype "passive"))
      (node (ref "C2") (pin "2") (pinfunction "2_2") (pintype "passive"))
      (node (ref "C3") (pin "2") (pinfunction "2_2") (pintype "passive"))
      (node (ref "C4") (pin "2") (pinfunction "2_2") (pintype "passive"))
      (node (ref "C42") (pin "2") (pinfunction "2_2") (pintype "passive"))
      (node (ref "C43") (pin "2") (pinfunction "2_2") (pintype "passive"))
      (node (ref "C44") (pin "2") (pinfunction "2_2") (pintype "passive"))
      (node (ref "C45") (pin "2") (pinfunction "2_2") (pintype "passive"))
      (node (ref "C46") (pin "2") (pinfunction "2_2") (pintype "passive"))
      (node (ref "C47") (pin "2") (pinfunction "2_2") (pintype "passive"))
      (node (ref "C48") (pin "2") (pinfunction "2_2") (pintype "passive"))
      (node (ref "C49") (pin "2") (pinfunction "2_2") (pintype "passive"))
      (node (ref "C5") (pin "2") (pinfunction "2_2") (pintype "passive"))
      (node (ref "C50") (pin "2") (pinfunction "2_2") (pintype "passive"))
      (node (ref "C51") (pin "2") (pinfunction "2_2") (pintype "passive"))
      (node (ref "C52") (pin "2") (pinfunction "2_2") (pintype "passive"))
      (node (ref "C53") (pin "2") (pinfunction "2_2") (pintype "passive"))
      (node (ref "C54") (pin "2") (pinfunction "2_2") (pintype "passive"))
      (node (ref "C55") (pin "2") (pinfunction "2_2") (pintype "passive"))
      (node (ref "C6") (pin "2") (pinfunction "2_2") (pintype "passive"))
      (node (ref "C7") (pin "2") (pinfunction "2_2") (pintype "passive"))
      (node (ref "C8") (pin "2") (pinfunction "2_2") (pintype "passive"))
      (node (ref "D1") (pin "1") (pinfunction "A_1") (pintype "passive"))
      (node (ref "D3") (pin "1") (pinfunction "A_1") (pintype "passive"))
      (node (ref "D4") (pin "1") (pinfunction "A_1") (pintype "passive"))
      (node (ref "D5") (pin "1") (pinfunction "A_1") (pintype "passive"))
      (node (ref "D7") (pin "1") (pinfunction "A_1") (pintype "passive"))
      (node (ref "D8") (pin "1") (pinfunction "A_1") (pintype "passive"))
      (node (ref "Q2") (pin "3") (pinfunction "S_3") (pintype "passive"))
      (node (ref "Q3") (pin "3") (pinfunction "S_3") (pintype "passive"))
      (node (ref "Q4") (pin "3") (pinfunction "S_3") (pintype "passive"))
      (node (ref "Q7") (pin "3") (pinfunction "S_3") (pintype "passive"))
      (node (ref "R10") (pin "2") (pinfunction "2_2") (pintype "passive"))
      (node (ref "R111") (pin "1") (pinfunction "1_1") (pintype "passive"))
      (node (ref "R112") (pin "1") (pinfunction "1_1") (pintype "passive"))
      (node (ref "R113") (pin "1") (pinfunction "1_1") (pintype "passive"))
      (node (ref "R114") (pin "1") (pinfunction "1_1") (pintype "passive"))
      (node (ref "R117") (pin "1") (pinfunction "1_1") (pintype "passive"))
      (node (ref "R118") (pin "1") (pinfunction "1_1") (pintype "passive"))
      (node (ref "R12") (pin "2") (pinfunction "2_2") (pintype "passive"))
      (node (ref "R122") (pin "2") (pinfunction "2_2") (pintype "passive"))
      (node (ref "R126") (pin "2") (pinfunction "2_2") (pintype "passive"))
      (node (ref "R127") (pin "2") (pinfunction "2_2") (pintype "passive"))
      (node (ref "R128") (pin "2") (pinfunction "2_2") (pintype "passive"))
      (node (ref "R13") (pin "2") (pinfunction "2_2") (pintype "passive"))
      (node (ref "R14") (pin "2") (pinfunction "2_2") (pintype "passive"))
      (node (ref "R15") (pin "2") (pinfunction "2_2") (pintype "passive"))
      (node (ref "R16") (pin "2") (pinfunction "2_2") (pintype "passive"))
      (node (ref "R23") (pin "1") (pinfunction "1_1") (pintype "passive"))
      (node (ref "R24") (pin "1") (pinfunction "1_1") (pintype "passive"))
      (node (ref "R26") (pin "1") (pinfunction "1_1") (pintype "passive"))
      (node (ref "R27") (pin "1") (pinfunction "1_1") (pintype "passive"))
      (node (ref "R28") (pin "1") (pinfunction "1_1") (pintype "passive"))
      (node (ref "R74") (pin "2") (pinfunction "2_2") (pintype "passive"))
      (node (ref "R75") (pin "2") (pinfunction "2_2") (pintype "passive"))
      (node (ref "R76") (pin "2") (pinfunction "2_2") (pintype "passive"))
      (node (ref "R77") (pin "2") (pinfunction "2_2") (pintype "passive"))
      (node (ref "R78") (pin "2") (pinfunction "2_2") (pintype "passive"))
      (node (ref "U10") (pin "6") (pinfunction "INH_6") (pintype "input"))
      (node (ref "U10") (pin "7") (pinfunction "VEE_7") (pintype "power_in"))
      (node (ref "U10") (pin "8") (pinfunction "VSS_8") (pintype "power_in"))
      (node (ref "U11") (pin "6") (pinfunction "INH_6") (pintype "input"))
      (node (ref "U11") (pin "7") (pinfunction "VEE_7") (pintype "power_in"))
      (node (ref "U11") (pin "8") (pinfunction "VSS_8") (pintype "power_in"))
      (node (ref "U4") (pin "6") (pinfunction "INH_6") (pintype "input"))
      (node (ref "U4") (pin "7") (pinfunction "VEE_7") (pintype "power_in"))
      (node (ref "U4") (pin "8") (pinfunction "VSS_8") (pintype "power_in"))
    )
    (net (code "64") (name "Net-(R92-Pad2)") (class "Default")
      (node (ref "R92") (pin "2") (pinfunction "2_2") (pintype "passive"))
      (node (ref "R93") (pin "1") (pinfunction "1_1") (pintype "passive"))
    )
    (net (code "65") (name "Net-(R94-Pad2)") (class "Default")
      (node (ref "R94") (pin "2") (pinfunction "2_2") (pintype "passive"))
      (node (ref "R95") (pin "1") (pinfunction "1_1") (pintype "passive"))
    )
    (net (code "66") (name "Net-(R96-Pad2)") (class "Default")
      (node (ref "R96") (pin "2") (pinfunction "2_2") (pintype "passive"))
      (node (ref "R97") (pin "1") (pinfunction "1_1") (pintype "passive"))
    )
    (net (code "67") (name "Net-(R98-Pad2)") (class "Default")
      (node (ref "R98") (pin "2") (pinfunction "2_2") (pintype "passive"))
      (node (ref "R99") (pin "1") (pinfunction "1_1") (pintype "passive"))
    )
    (net (code "68") (name "unconnected-(U11-X0-Pad13)") (class "Default")
      (node (ref "U11") (pin "13") (pinfunction "X0_13") (pintype "bidirectional"))
    )
    (net (code "69") (name "unconnected-(U11-X6-Pad2)") (class "Default")
      (node (ref "U11") (pin "2") (pinfunction "X6_2") (pintype "bidirectional"))
    )
    (net (code "70") (name "unconnected-(U11-X7-Pad4)") (class "Default")
      (node (ref "U11") (pin "4") (pinfunction "X7_4") (pintype "bidirectional"))
    )
  )
)
